# FD_Capacitance_Sensor_v18.net
KiCad netlist of a schematic drawn in EAGLE
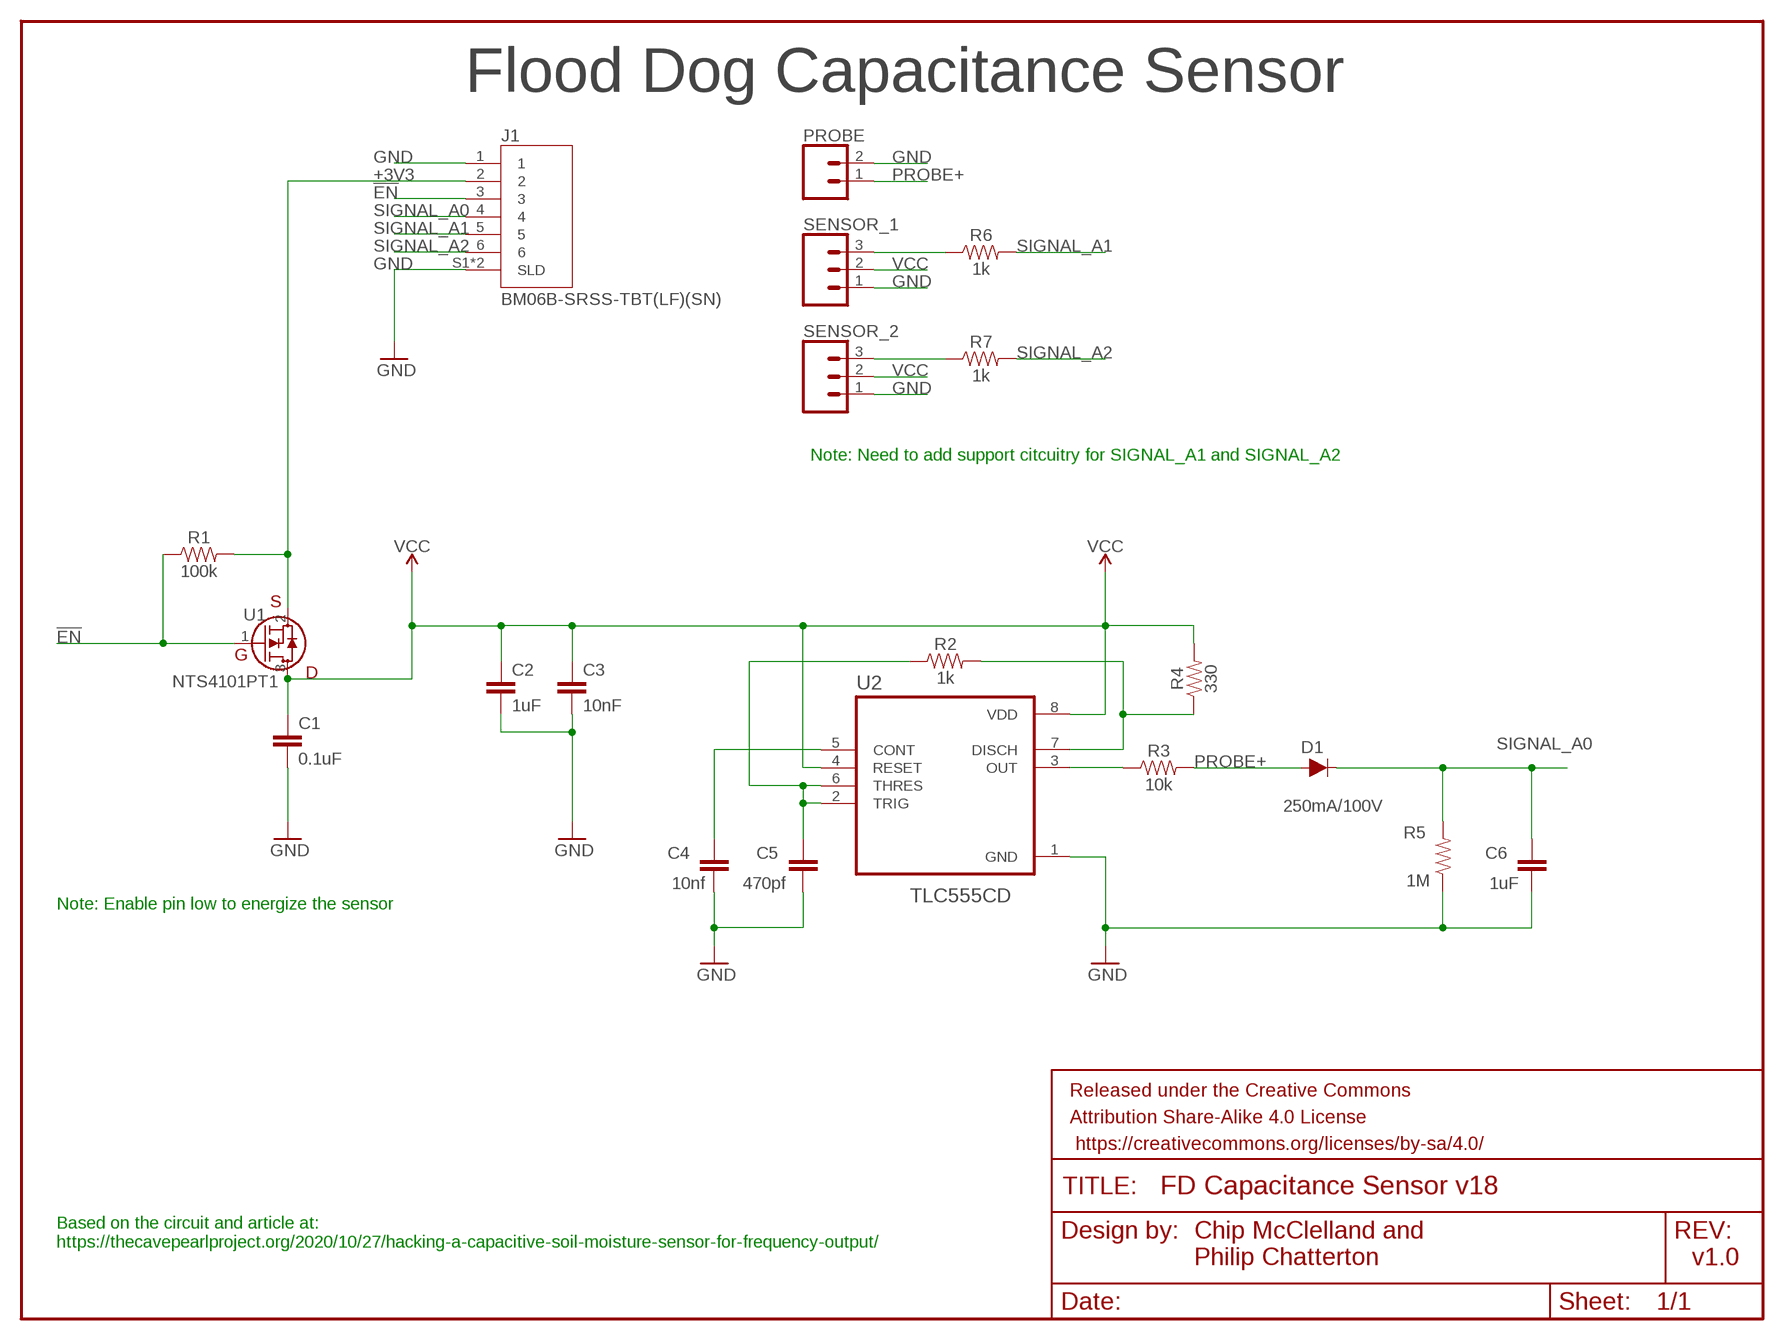
[diagram p0: schematic, sheet 1]

(export (version "E")
  (design (tool "Eeschema 10.0.6"))
  (components
    (comp (ref "C1")
      (value "0.1uF")
      (footprint "eagle-import:0805@1")
      (fields (field (name "HOUSEPART") "YES") (field (name "MPN") "MF-CAP-0805-0.1uF"))
      (libsource (lib "eagle-import") (part "CAP-MF-0.1UF-0805"))
    )
    (comp (ref "C2")
      (value "1uF")
      (footprint "eagle-import:0805@1")
      (fields (field (name "HOUSEPART") "yes") (field (name "MPN") "MF-CAP-0805-1uF"))
      (libsource (lib "eagle-import") (part "CAP-MF-1UF-0805"))
    )
    (comp (ref "C3")
      (value "10nF")
      (footprint "eagle-import:0805@1")
      (fields (field (name "HOUSEPART") "NO") (field (name "MPN") "C0805X103K1RAC3316"))
      (libsource (lib "eagle-import") (part "CAP-10NF-0805"))
    )
    (comp (ref "C4")
      (value "10nf")
      (footprint "eagle-import:C0805")
      (libsource (lib "eagle-import") (part "C-EUC0805"))
    )
    (comp (ref "C5")
      (value "470pf")
      (footprint "eagle-import:C0805")
      (libsource (lib "eagle-import") (part "C-EUC0805"))
    )
    (comp (ref "C6")
      (value "1uF")
      (footprint "eagle-import:C0805")
      (libsource (lib "eagle-import") (part "C-EUC0805"))
    )
    (comp (ref "D1")
      (value "250mA/100V")
      (footprint "eagle-import:SOD-323")
      (fields (field (name "MPN") "BAS16HT1G"))
      (libsource (lib "eagle-import") (part "DIODE-BAS16J"))
    )
    (comp (ref "FRAME1")
      (value "FRAME-LETTERNO_PACKAGE")
      (footprint "eagle-import:DUMMY")
      (fields (field (name "DESIGNER") "Nobody"))
      (libsource (lib "eagle-import") (part "FRAME-LETTERNO_PACKAGE"))
    )
    (comp (ref "J1")
      (value "BM06B-SRSS-TBT(LF)(SN)")
      (footprint "eagle-import:JST_BM06B-SRSS-TB(LF)(SN)")
      (libsource (lib "eagle-import") (part "BM06B-SRSS-TBT(LF)(SN)"))
    )
    (comp (ref "PROBE")
      (value "CONN_02")
      (footprint "eagle-import:1X02")
      (libsource (lib "eagle-import") (part "CONN_02"))
    )
    (comp (ref "R1")
      (value "100k")
      (footprint "eagle-import:0805")
      (fields (field (name "MPN") "MF-RES-0805-100K") (field (name "MPN_1") "MF-RES-0805-100K"))
      (libsource (lib "eagle-import") (part "RESISTOR-MF-100K-0805"))
    )
    (comp (ref "R2")
      (value "1k")
      (footprint "eagle-import:0805")
      (fields (field (name "HOUSEPART") "YES") (field (name "MPN") "MF-RES-0805-1K"))
      (libsource (lib "eagle-import") (part "RESISTOR-MF-1K-0805"))
    )
    (comp (ref "R3")
      (value "10k")
      (footprint "eagle-import:0805")
      (fields (field (name "MPN") "MF-RES-0805-10K"))
      (libsource (lib "eagle-import") (part "RESISTOR-MF-10K-0805"))
    )
    (comp (ref "R4")
      (value "330")
      (footprint "eagle-import:0805")
      (fields (field (name "HOUSEPART") "YES") (field (name "MPN") "MF-RES-0805-330"))
      (libsource (lib "eagle-import") (part "RESISTOR-MF-330-0805"))
    )
    (comp (ref "R5")
      (value "1M")
      (footprint "eagle-import:0805")
      (fields (field (name "HOUSEPART") "YES") (field (name "MPN") "MF-RES-0805-1K"))
      (libsource (lib "eagle-import") (part "RESISTOR-MF-1K-0805"))
    )
    (comp (ref "R6")
      (value "1k")
      (footprint "eagle-import:0805")
      (fields (field (name "HOUSEPART") "YES") (field (name "MPN") "MF-RES-0805-1K"))
      (libsource (lib "eagle-import") (part "RESISTOR-MF-1K-0805"))
    )
    (comp (ref "R7")
      (value "1k")
      (footprint "eagle-import:0805")
      (fields (field (name "HOUSEPART") "YES") (field (name "MPN") "MF-RES-0805-1K"))
      (libsource (lib "eagle-import") (part "RESISTOR-MF-1K-0805"))
    )
    (comp (ref "SENSOR_1")
      (value "CONN_03")
      (footprint "eagle-import:1X03")
      (libsource (lib "eagle-import") (part "CONN_03"))
    )
    (comp (ref "SENSOR_2")
      (value "CONN_03")
      (footprint "eagle-import:1X03")
      (libsource (lib "eagle-import") (part "CONN_03"))
    )
    (comp (ref "U1")
      (value "NTS4101PT1")
      (footprint "eagle-import:SOT_101PT1_ONS")
      (libsource (lib "eagle-import") (part "NTS4101PT1"))
    )
    (comp (ref "U2")
      (value "TLC555CD")
      (footprint "eagle-import:SOIC127P599X175-8N")
      (fields (field (name "DIGI-KEY_PART_NUMBER") "296-52992-ND") (field (name "MF") "Texas Instruments"))
      (libsource (lib "eagle-import") (part "TLC555CD"))
    )
  )
  (nets
    (net (code "1") (name "/+3V3") (class "Default")
      (node (ref "J1") (pin "2") (pinfunction "2_2") (pintype "passive"))
      (node (ref "R1") (pin "2") (pinfunction "2_2") (pintype "passive"))
      (node (ref "U1") (pin "2") (pinfunction "S_2") (pintype "passive"))
    )
    (net (code "2") (name "/PROBE+") (class "Default")
      (node (ref "D1") (pin "A") (pinfunction "A_A") (pintype "passive"))
      (node (ref "PROBE") (pin "1") (pinfunction "1_1") (pintype "passive"))
      (node (ref "R3") (pin "2") (pinfunction "2_2") (pintype "passive"))
    )
    (net (code "3") (name "/SIGNAL_A0") (class "Default")
      (node (ref "C6") (pin "2") (pinfunction "2_2") (pintype "passive"))
      (node (ref "D1") (pin "C") (pinfunction "C_C") (pintype "passive"))
      (node (ref "J1") (pin "4") (pinfunction "4_4") (pintype "passive"))
      (node (ref "R5") (pin "2") (pinfunction "2_2") (pintype "passive"))
    )
    (net (code "4") (name "/SIGNAL_A1") (class "Default")
      (node (ref "J1") (pin "5") (pinfunction "5_5") (pintype "passive"))
      (node (ref "R6") (pin "2") (pinfunction "2_2") (pintype "passive"))
    )
    (net (code "5") (name "/SIGNAL_A2") (class "Default")
      (node (ref "J1") (pin "6") (pinfunction "6_6") (pintype "passive"))
      (node (ref "R7") (pin "2") (pinfunction "2_2") (pintype "passive"))
    )
    (net (code "6") (name "/~{EN}") (class "Default")
      (node (ref "J1") (pin "3") (pinfunction "3_3") (pintype "passive"))
      (node (ref "R1") (pin "1") (pinfunction "1_1") (pintype "passive"))
      (node (ref "U1") (pin "1") (pinfunction "G_1") (pintype "passive"))
    )
    (net (code "7") (name "GND") (class "Default")
      (node (ref "C1") (pin "2") (pinfunction "2_2") (pintype "passive"))
      (node (ref "C2") (pin "2") (pinfunction "2_2") (pintype "passive"))
      (node (ref "C3") (pin "2") (pinfunction "2_2") (pintype "passive"))
      (node (ref "C4") (pin "1") (pinfunction "1_1") (pintype "passive"))
      (node (ref "C5") (pin "1") (pinfunction "1_1") (pintype "passive"))
      (node (ref "C6") (pin "1") (pinfunction "1_1") (pintype "passive"))
      (node (ref "J1") (pin "1") (pinfunction "1_1") (pintype "passive"))
      (node (ref "J1") (pin "S1") (pinfunction "SLD_S1") (pintype "passive"))
      (node (ref "J1") (pin "S2") (pinfunction "SLD_S2") (pintype "passive"))
      (node (ref "PROBE") (pin "2") (pinfunction "2_2") (pintype "passive"))
      (node (ref "R5") (pin "1") (pinfunction "1_1") (pintype "passive"))
      (node (ref "SENSOR_1") (pin "1") (pinfunction "1_1") (pintype "passive"))
      (node (ref "SENSOR_2") (pin "1") (pinfunction "1_1") (pintype "passive"))
      (node (ref "U2") (pin "1") (pinfunction "GND_1") (pintype "power_in"))
    )
    (net (code "8") (name "Net-(R6-Pad1)") (class "Default")
      (node (ref "R6") (pin "1") (pinfunction "1_1") (pintype "passive"))
      (node (ref "SENSOR_1") (pin "3") (pinfunction "3_3") (pintype "passive"))
    )
    (net (code "9") (name "Net-(R7-Pad1)") (class "Default")
      (node (ref "R7") (pin "1") (pinfunction "1_1") (pintype "passive"))
      (node (ref "SENSOR_2") (pin "3") (pinfunction "3_3") (pintype "passive"))
    )
    (net (code "10") (name "Net-(U2-CONT)") (class "Default")
      (node (ref "C4") (pin "2") (pinfunction "2_2") (pintype "passive"))
      (node (ref "U2") (pin "5") (pinfunction "CONT_5") (pintype "input"))
    )
    (net (code "11") (name "Net-(U2-DISCH)") (class "Default")
      (node (ref "R2") (pin "2") (pinfunction "2_2") (pintype "passive"))
      (node (ref "R4") (pin "1") (pinfunction "1_1") (pintype "passive"))
      (node (ref "U2") (pin "7") (pinfunction "DISCH_7") (pintype "output"))
    )
    (net (code "12") (name "Net-(U2-OUT)") (class "Default")
      (node (ref "R3") (pin "1") (pinfunction "1_1") (pintype "passive"))
      (node (ref "U2") (pin "3") (pinfunction "OUT_3") (pintype "output"))
    )
    (net (code "13") (name "Net-(U2-THRES)") (class "Default")
      (node (ref "C5") (pin "2") (pinfunction "2_2") (pintype "passive"))
      (node (ref "R2") (pin "1") (pinfunction "1_1") (pintype "passive"))
      (node (ref "U2") (pin "2") (pinfunction "TRIG_2") (pintype "input"))
      (node (ref "U2") (pin "6") (pinfunction "THRES_6") (pintype "input"))
    )
    (net (code "14") (name "VCC") (class "Default")
      (node (ref "C1") (pin "1") (pinfunction "1_1") (pintype "passive"))
      (node (ref "C2") (pin "1") (pinfunction "1_1") (pintype "passive"))
      (node (ref "C3") (pin "1") (pinfunction "1_1") (pintype "passive"))
      (node (ref "R4") (pin "2") (pinfunction "2_2") (pintype "passive"))
      (node (ref "SENSOR_1") (pin "2") (pinfunction "2_2") (pintype "passive"))
      (node (ref "SENSOR_2") (pin "2") (pinfunction "2_2") (pintype "passive"))
      (node (ref "U1") (pin "3") (pinfunction "D_3") (pintype "passive"))
      (node (ref "U2") (pin "4") (pinfunction "RESET_4") (pintype "input"))
      (node (ref "U2") (pin "8") (pinfunction "VDD_8") (pintype "power_in"))
    )
  )
)
